# lockcontroller_V2.net
KiCad netlist of a schematic drawn in EAGLE
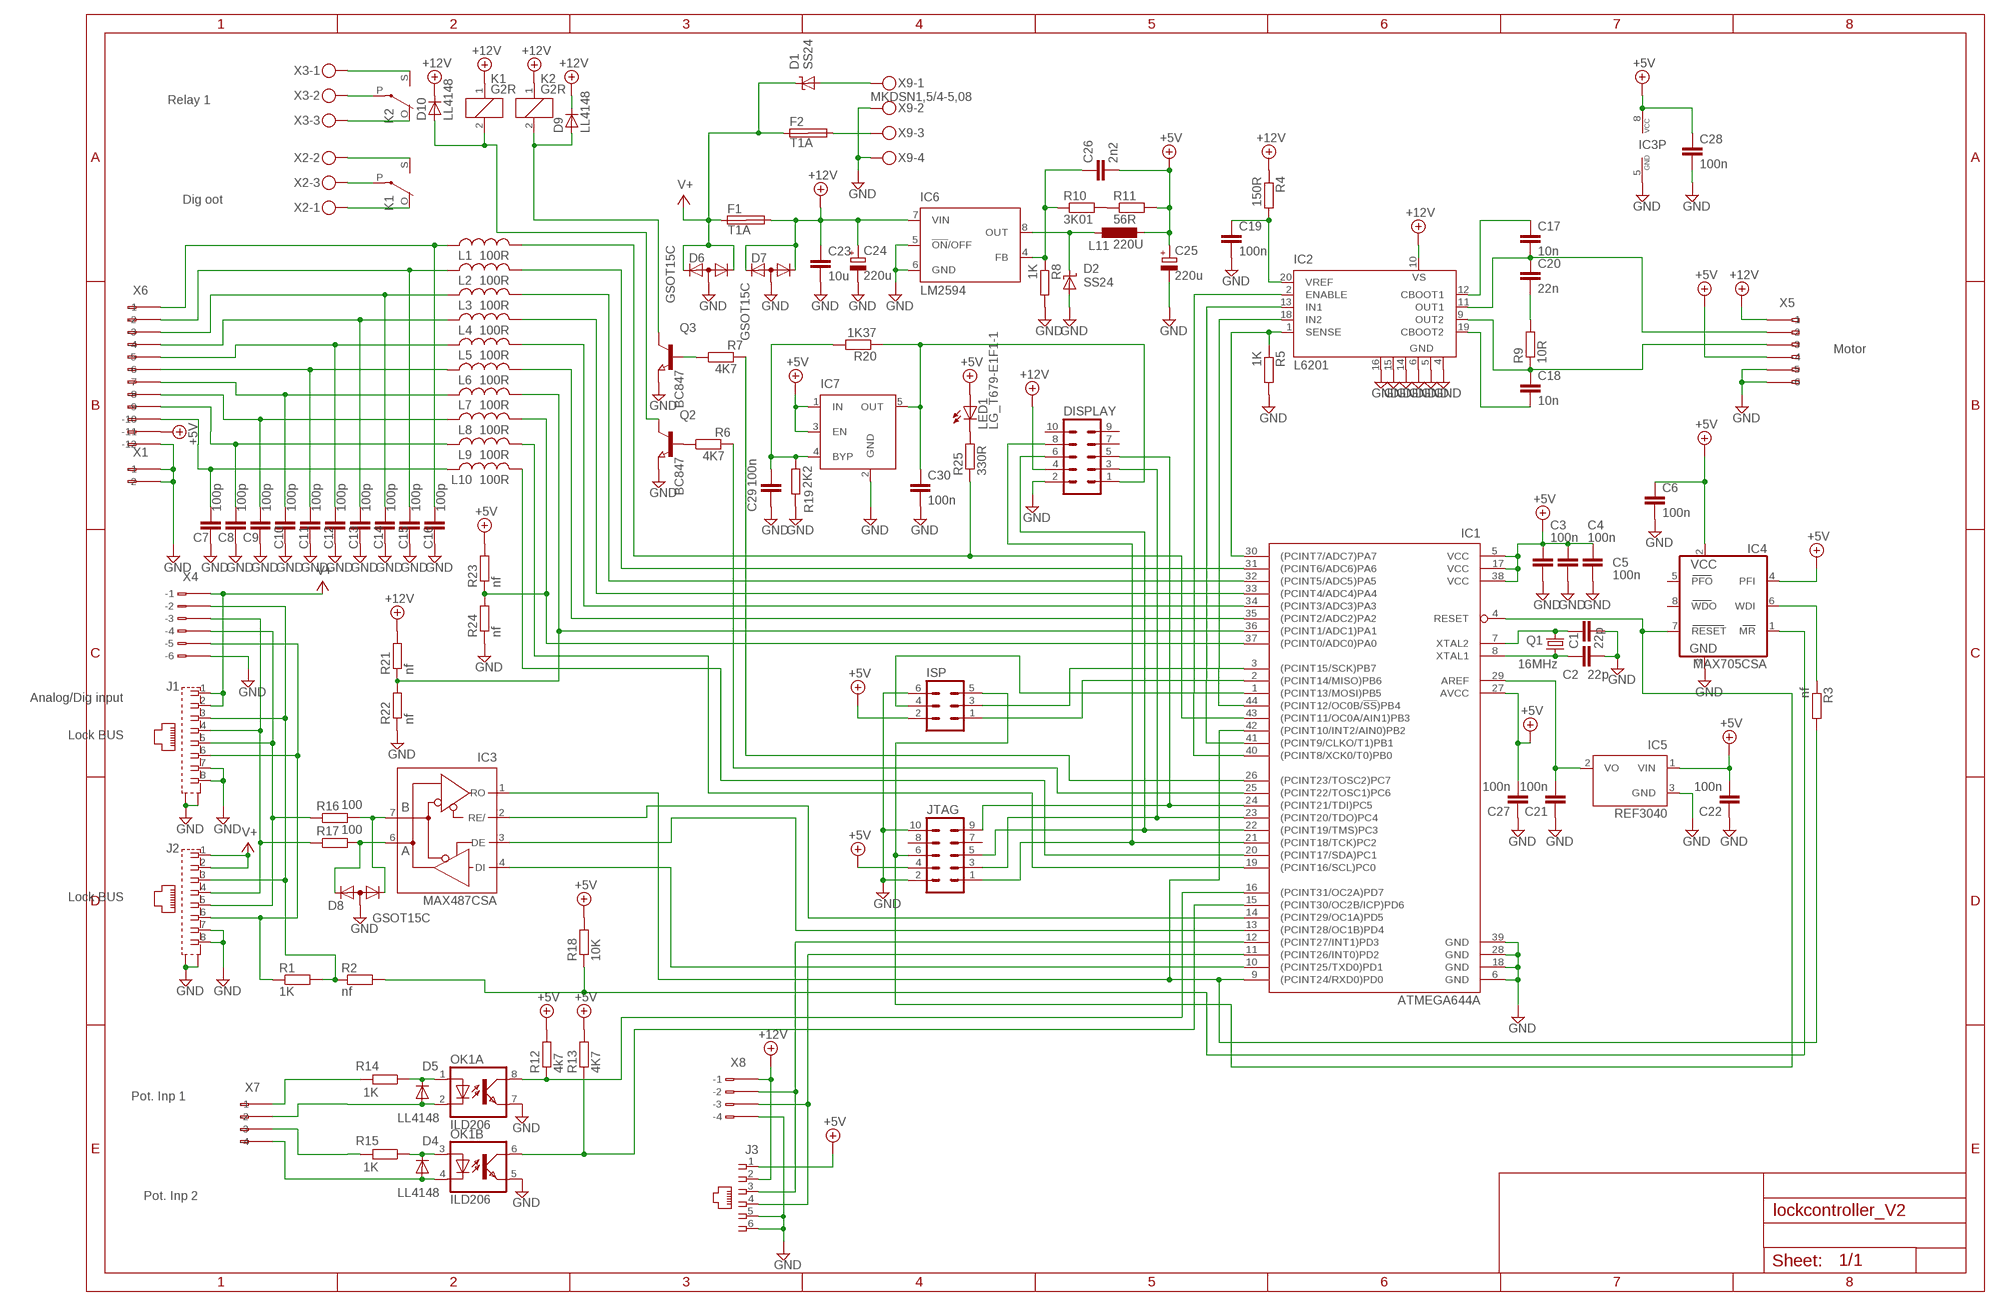
[diagram p0: schematic, sheet 1]

(export (version "E")
  (design (tool "Eeschema 10.0.6"))
  (components
    (comp (ref "C1")
      (value "22p")
      (footprint "eagle-import:C0603")
      (libsource (lib "eagle-import") (part "C-EUC0603"))
    )
    (comp (ref "C2")
      (value "22p")
      (footprint "eagle-import:C0603")
      (libsource (lib "eagle-import") (part "C-EUC0603"))
    )
    (comp (ref "C3")
      (value "100n")
      (footprint "eagle-import:C0603")
      (libsource (lib "eagle-import") (part "C-EUC0603"))
    )
    (comp (ref "C4")
      (value "100n")
      (footprint "eagle-import:C0603")
      (libsource (lib "eagle-import") (part "C-EUC0603"))
    )
    (comp (ref "C5")
      (value "100n")
      (footprint "eagle-import:C0603")
      (libsource (lib "eagle-import") (part "C-EUC0603"))
    )
    (comp (ref "C6")
      (value "100n")
      (footprint "eagle-import:C0603")
      (libsource (lib "eagle-import") (part "C-EUC0603"))
    )
    (comp (ref "C7")
      (value "100p")
      (footprint "eagle-import:C0603")
      (libsource (lib "eagle-import") (part "C-EUC0603"))
    )
    (comp (ref "C8")
      (value "100p")
      (footprint "eagle-import:C0603")
      (libsource (lib "eagle-import") (part "C-EUC0603"))
    )
    (comp (ref "C9")
      (value "100p")
      (footprint "eagle-import:C0603")
      (libsource (lib "eagle-import") (part "C-EUC0603"))
    )
    (comp (ref "C10")
      (value "100p")
      (footprint "eagle-import:C0603")
      (libsource (lib "eagle-import") (part "C-EUC0603"))
    )
    (comp (ref "C11")
      (value "100p")
      (footprint "eagle-import:C0603")
      (libsource (lib "eagle-import") (part "C-EUC0603"))
    )
    (comp (ref "C12")
      (value "100p")
      (footprint "eagle-import:C0603")
      (libsource (lib "eagle-import") (part "C-EUC0603"))
    )
    (comp (ref "C13")
      (value "100p")
      (footprint "eagle-import:C0603")
      (libsource (lib "eagle-import") (part "C-EUC0603"))
    )
    (comp (ref "C14")
      (value "100p")
      (footprint "eagle-import:C0603")
      (libsource (lib "eagle-import") (part "C-EUC0603"))
    )
    (comp (ref "C15")
      (value "100p")
      (footprint "eagle-import:C0603")
      (libsource (lib "eagle-import") (part "C-EUC0603"))
    )
    (comp (ref "C16")
      (value "100p")
      (footprint "eagle-import:C0603")
      (libsource (lib "eagle-import") (part "C-EUC0603"))
    )
    (comp (ref "C17")
      (value "10n")
      (footprint "eagle-import:C1206")
      (libsource (lib "eagle-import") (part "C-EUC1206"))
    )
    (comp (ref "C18")
      (value "10n")
      (footprint "eagle-import:C1206")
      (libsource (lib "eagle-import") (part "C-EUC1206"))
    )
    (comp (ref "C19")
      (value "100n")
      (footprint "eagle-import:C0603")
      (libsource (lib "eagle-import") (part "C-EUC0603"))
    )
    (comp (ref "C20")
      (value "22n")
      (footprint "eagle-import:C1206")
      (libsource (lib "eagle-import") (part "C-EUC1206"))
    )
    (comp (ref "C21")
      (value "100n")
      (footprint "eagle-import:C0603")
      (libsource (lib "eagle-import") (part "C-EUC0603"))
    )
    (comp (ref "C22")
      (value "100n")
      (footprint "eagle-import:C0603")
      (libsource (lib "eagle-import") (part "C-EUC0603"))
    )
    (comp (ref "C23")
      (value "10u")
      (footprint "eagle-import:C1210")
      (libsource (lib "eagle-import") (part "C-EUC1210"))
    )
    (comp (ref "C24")
      (value "220u")
      (footprint "eagle-import:E5-8,5")
      (libsource (lib "eagle-import") (part "CPOL-EUE5-8.5"))
    )
    (comp (ref "C25")
      (value "220u")
      (footprint "eagle-import:E5-8,5")
      (libsource (lib "eagle-import") (part "CPOL-EUE5-8.5"))
    )
    (comp (ref "C26")
      (value "2n2")
      (footprint "eagle-import:C0603")
      (libsource (lib "eagle-import") (part "C-EUC0603"))
    )
    (comp (ref "C27")
      (value "100n")
      (footprint "eagle-import:C0603")
      (libsource (lib "eagle-import") (part "C-EUC0603"))
    )
    (comp (ref "C28")
      (value "100n")
      (footprint "eagle-import:C0603")
      (libsource (lib "eagle-import") (part "C-EUC0603"))
    )
    (comp (ref "C29")
      (value "100n")
      (footprint "eagle-import:C0603")
      (libsource (lib "eagle-import") (part "C-EUC0603"))
    )
    (comp (ref "C30")
      (value "100n")
      (footprint "eagle-import:C0603")
      (libsource (lib "eagle-import") (part "C-EUC0603"))
    )
    (comp (ref "D1")
      (value "SS24")
      (footprint "eagle-import:SMBG")
      (libsource (lib "eagle-import") (part "SUPPRESSOR-SMBG"))
    )
    (comp (ref "D2")
      (value "SS24")
      (footprint "eagle-import:SMBG")
      (libsource (lib "eagle-import") (part "SUPPRESSOR-SMBG"))
    )
    (comp (ref "D4")
      (value "LL4148")
      (footprint "eagle-import:MELF-MLL34")
      (libsource (lib "eagle-import") (part "D-MLL-34"))
    )
    (comp (ref "D5")
      (value "LL4148")
      (footprint "eagle-import:MELF-MLL34")
      (libsource (lib "eagle-import") (part "D-MLL-34"))
    )
    (comp (ref "D6")
      (value "GSOT15C")
      (footprint "eagle-import:SOT23C")
      (libsource (lib "eagle-import") (part "DIODE_CA-AC__"))
    )
    (comp (ref "D7")
      (value "GSOT15C")
      (footprint "eagle-import:SOT23C")
      (libsource (lib "eagle-import") (part "DIODE_CA-AC__"))
    )
    (comp (ref "D8")
      (value "GSOT15C")
      (footprint "eagle-import:SOT23C")
      (libsource (lib "eagle-import") (part "DIODE_CA-AC__"))
    )
    (comp (ref "D9")
      (value "LL4148")
      (footprint "eagle-import:MELF-MLL34")
      (libsource (lib "eagle-import") (part "D-MLL-34"))
    )
    (comp (ref "D10")
      (value "LL4148")
      (footprint "eagle-import:MELF-MLL34")
      (libsource (lib "eagle-import") (part "D-MLL-34"))
    )
    (comp (ref "DISPLAY")
      (value "MA05-2")
      (footprint "eagle-import:MA05-2")
      (libsource (lib "eagle-import") (part "MA05-2"))
    )
    (comp (ref "F1")
      (value "T1A")
      (footprint "eagle-import:SHK20L")
      (libsource (lib "eagle-import") (part "SHK20L"))
    )
    (comp (ref "F2")
      (value "T1A")
      (footprint "eagle-import:SHK20L")
      (libsource (lib "eagle-import") (part "SHK20L"))
    )
    (comp (ref "IC1")
      (value "ATMEGA644A")
      (footprint "eagle-import:TQFP44")
      (libsource (lib "eagle-import") (part "ATMEGA644A"))
    )
    (comp (ref "IC2")
      (value "L6201")
      (footprint "eagle-import:SO20")
      (libsource (lib "eagle-import") (part "L6201"))
    )
    (comp (ref "IC3")
      (value "MAX487CSA")
      (footprint "eagle-import:SO08")
      (libsource (lib "eagle-import") (part "MAX481CSA"))
    )
    (comp (ref "IC4")
      (value "MAX705CSA")
      (footprint "eagle-import:SO08")
      (libsource (lib "eagle-import") (part "MAX705CSA"))
    )
    (comp (ref "IC5")
      (value "REF3040")
      (footprint "eagle-import:SOT23")
      (libsource (lib "eagle-import") (part "MC15TT25"))
    )
    (comp (ref "IC6")
      (value "LM2594")
      (footprint "eagle-import:SO08")
      (libsource (lib "eagle-import") (part "LM2594"))
    )
    (comp (ref "IC7")
      (value "MIC5219XX")
      (footprint "eagle-import:SOT23-5")
      (libsource (lib "eagle-import") (part "MIC5219XX"))
    )
    (comp (ref "ISP")
      (value "MA03-2")
      (footprint "eagle-import:MA03-2")
      (libsource (lib "eagle-import") (part "MA03-2"))
    )
    (comp (ref "J1")
      (value "555141-1")
      (footprint "eagle-import:555153-1")
      (libsource (lib "eagle-import") (part "555141-1"))
    )
    (comp (ref "J2")
      (value "555141-1")
      (footprint "eagle-import:555153-1")
      (libsource (lib "eagle-import") (part "555141-1"))
    )
    (comp (ref "J3")
      (value "520250-3")
      (footprint "eagle-import:520250-3")
      (libsource (lib "eagle-import") (part "520250-3"))
    )
    (comp (ref "JTAG")
      (value "MA05-2")
      (footprint "eagle-import:MA05-2")
      (libsource (lib "eagle-import") (part "MA05-2"))
    )
    (comp (ref "K1")
      (value "G2R")
      (footprint "eagle-import:G2R")
      (libsource (lib "eagle-import") (part "G2R"))
    )
    (comp (ref "K2")
      (value "G2R")
      (footprint "eagle-import:G2R")
      (libsource (lib "eagle-import") (part "G2R"))
    )
    (comp (ref "L1")
      (value "100R")
      (footprint "eagle-import:R0603")
      (libsource (lib "eagle-import") (part "L-US0603"))
    )
    (comp (ref "L2")
      (value "100R")
      (footprint "eagle-import:R0603")
      (libsource (lib "eagle-import") (part "L-US0603"))
    )
    (comp (ref "L3")
      (value "100R")
      (footprint "eagle-import:R0603")
      (libsource (lib "eagle-import") (part "L-US0603"))
    )
    (comp (ref "L4")
      (value "100R")
      (footprint "eagle-import:R0603")
      (libsource (lib "eagle-import") (part "L-US0603"))
    )
    (comp (ref "L5")
      (value "100R")
      (footprint "eagle-import:R0603")
      (libsource (lib "eagle-import") (part "L-US0603"))
    )
    (comp (ref "L6")
      (value "100R")
      (footprint "eagle-import:R0603")
      (libsource (lib "eagle-import") (part "L-US0603"))
    )
    (comp (ref "L7")
      (value "100R")
      (footprint "eagle-import:R0603")
      (libsource (lib "eagle-import") (part "L-US0603"))
    )
    (comp (ref "L8")
      (value "100R")
      (footprint "eagle-import:R0603")
      (libsource (lib "eagle-import") (part "L-US0603"))
    )
    (comp (ref "L9")
      (value "100R")
      (footprint "eagle-import:R0603")
      (libsource (lib "eagle-import") (part "L-US0603"))
    )
    (comp (ref "L10")
      (value "100R")
      (footprint "eagle-import:R0603")
      (libsource (lib "eagle-import") (part "L-US0603"))
    )
    (comp (ref "L11")
      (value "220U")
      (footprint "eagle-import:DO3316P")
      (libsource (lib "eagle-import") (part "DO3316P"))
    )
    (comp (ref "LED1")
      (value "LG_T679-E1F1-1")
      (footprint "eagle-import:PLCC2")
      (libsource (lib "eagle-import") (part "_T679-?-1E1F1LG"))
    )
    (comp (ref "OK1")
      (value "ILD206")
      (footprint "eagle-import:SOIC08")
      (libsource (lib "eagle-import") (part "ILD206"))
    )
    (comp (ref "Q1")
      (value "16MHz")
      (footprint "eagle-import:HC49_S")
      (libsource (lib "eagle-import") (part "CRYSTALHC49S"))
    )
    (comp (ref "Q2")
      (value "BC847")
      (footprint "eagle-import:SOT23")
      (libsource (lib "eagle-import") (part "NPN-TRANSISTOR_SOT23"))
    )
    (comp (ref "Q3")
      (value "BC847")
      (footprint "eagle-import:SOT23")
      (libsource (lib "eagle-import") (part "NPN-TRANSISTOR_SOT23"))
    )
    (comp (ref "R1")
      (value "1K")
      (footprint "eagle-import:R0603")
      (libsource (lib "eagle-import") (part "R-EU_R0603"))
    )
    (comp (ref "R2")
      (value "nf")
      (footprint "eagle-import:R0603")
      (libsource (lib "eagle-import") (part "R-EU_R0603"))
    )
    (comp (ref "R3")
      (value "nf")
      (footprint "eagle-import:R0603")
      (libsource (lib "eagle-import") (part "R-EU_R0603"))
    )
    (comp (ref "R4")
      (value "150R")
      (footprint "eagle-import:R0603")
      (libsource (lib "eagle-import") (part "R-EU_R0603"))
    )
    (comp (ref "R5")
      (value "1K")
      (footprint "eagle-import:R0603")
      (libsource (lib "eagle-import") (part "R-EU_R0603"))
    )
    (comp (ref "R6")
      (value "4K7")
      (footprint "eagle-import:R0603")
      (libsource (lib "eagle-import") (part "R-EU_R0603"))
    )
    (comp (ref "R7")
      (value "4K7")
      (footprint "eagle-import:R0603")
      (libsource (lib "eagle-import") (part "R-EU_R0603"))
    )
    (comp (ref "R8")
      (value "1K")
      (footprint "eagle-import:R0603")
      (libsource (lib "eagle-import") (part "R-EU_R0603"))
    )
    (comp (ref "R9")
      (value "10R")
      (footprint "eagle-import:R1206")
      (libsource (lib "eagle-import") (part "R-EU_R1206"))
    )
    (comp (ref "R10")
      (value "3K01")
      (footprint "eagle-import:R0603")
      (libsource (lib "eagle-import") (part "R-EU_R0603"))
    )
    (comp (ref "R11")
      (value "56R")
      (footprint "eagle-import:R0603")
      (libsource (lib "eagle-import") (part "R-EU_R0603"))
    )
    (comp (ref "R12")
      (value "4k7")
      (footprint "eagle-import:R0603")
      (libsource (lib "eagle-import") (part "R-EU_R0603"))
    )
    (comp (ref "R13")
      (value "4K7")
      (footprint "eagle-import:R0603")
      (libsource (lib "eagle-import") (part "R-EU_R0603"))
    )
    (comp (ref "R14")
      (value "1K")
      (footprint "eagle-import:R0603")
      (libsource (lib "eagle-import") (part "R-EU_R0603"))
    )
    (comp (ref "R15")
      (value "1K")
      (footprint "eagle-import:R0603")
      (libsource (lib "eagle-import") (part "R-EU_R0603"))
    )
    (comp (ref "R16")
      (value "100")
      (footprint "eagle-import:R0603")
      (libsource (lib "eagle-import") (part "R-EU_R0603"))
    )
    (comp (ref "R17")
      (value "100")
      (footprint "eagle-import:R0603")
      (libsource (lib "eagle-import") (part "R-EU_R0603"))
    )
    (comp (ref "R18")
      (value "10K")
      (footprint "eagle-import:R0603")
      (libsource (lib "eagle-import") (part "R-EU_R0603"))
    )
    (comp (ref "R19")
      (value "2K2")
      (footprint "eagle-import:R0603")
      (libsource (lib "eagle-import") (part "R-EU_R0603"))
    )
    (comp (ref "R20")
      (value "1K37")
      (footprint "eagle-import:R0603")
      (libsource (lib "eagle-import") (part "R-EU_R0603"))
    )
    (comp (ref "R21")
      (value "nf")
      (footprint "eagle-import:R0603")
      (libsource (lib "eagle-import") (part "R-EU_R0603"))
    )
    (comp (ref "R22")
      (value "nf")
      (footprint "eagle-import:R0603")
      (libsource (lib "eagle-import") (part "R-EU_R0603"))
    )
    (comp (ref "R23")
      (value "nf")
      (footprint "eagle-import:R0603")
      (libsource (lib "eagle-import") (part "R-EU_R0603"))
    )
    (comp (ref "R24")
      (value "nf")
      (footprint "eagle-import:R0603")
      (libsource (lib "eagle-import") (part "R-EU_R0603"))
    )
    (comp (ref "R25")
      (value "330R")
      (footprint "eagle-import:R0603")
      (libsource (lib "eagle-import") (part "R-EU_R0603"))
    )
    (comp (ref "X1")
      (value "233-502")
      (footprint "eagle-import:233-502")
      (libsource (lib "eagle-import") (part "233-502"))
    )
    (comp (ref "X2")
      (value "MKDSN1,5/3-5,08")
      (footprint "eagle-import:MKDSN1,5_3-5,08")
      (fields (field (name "MPN") "SMKDSN1,5/3-5,08"))
      (libsource (lib "eagle-import") (part "MKDSN1,5/3-5,08"))
    )
    (comp (ref "X3")
      (value "MKDSN1,5/3-5,08")
      (footprint "eagle-import:MKDSN1,5_3-5,08")
      (fields (field (name "MPN") "SMKDSN1,5/3-5,08"))
      (libsource (lib "eagle-import") (part "MKDSN1,5/3-5,08"))
    )
    (comp (ref "X4")
      (value "233-506")
      (footprint "eagle-import:233-506")
      (fields (field (name "MF") "Wago Corporation") (field (name "MPN") "0233-0506"))
      (libsource (lib "eagle-import") (part "233-506"))
    )
    (comp (ref "X5")
      (value "233-506")
      (footprint "eagle-import:233-506")
      (fields (field (name "MF") "Wago Corporation") (field (name "MPN") "0233-0506"))
      (libsource (lib "eagle-import") (part "con-wago255_233-506"))
    )
    (comp (ref "X6")
      (value "233-512")
      (footprint "eagle-import:233-512")
      (fields (field (name "MF") "Wago Corporation") (field (name "MPN") "0233-0512"))
      (libsource (lib "eagle-import") (part "233-512"))
    )
    (comp (ref "X7")
      (value "233-504")
      (footprint "eagle-import:233-504")
      (fields (field (name "MF") "Wago Corporation") (field (name "MPN") "0233-0504"))
      (libsource (lib "eagle-import") (part "con-wago255_233-504"))
    )
    (comp (ref "X8")
      (value "233-504")
      (footprint "eagle-import:233-504")
      (fields (field (name "MF") "Wago Corporation") (field (name "MPN") "0233-0504"))
      (libsource (lib "eagle-import") (part "233-504"))
    )
    (comp (ref "X9")
      (value "MKDSN1,5/4-5,08")
      (footprint "eagle-import:MKDSN1,5_4-5,08")
      (fields (field (name "MPN") "SMKDSN1,5/4-5,08"))
      (libsource (lib "eagle-import") (part "MKDSN1,5/4-5,08"))
    )
  )
  (nets
    (net (code "1") (name "+5V") (class "Default")
      (node (ref "C22") (pin "2") (pinfunction "2_2") (pintype "passive"))
      (node (ref "C25") (pin "+") (pinfunction "+_+") (pintype "passive"))
      (node (ref "C26") (pin "2") (pinfunction "2_2") (pintype "passive"))
      (node (ref "C27") (pin "2") (pinfunction "2_2") (pintype "passive"))
      (node (ref "C28") (pin "1") (pinfunction "1_1") (pintype "passive"))
      (node (ref "C3") (pin "1") (pinfunction "1_1") (pintype "passive"))
      (node (ref "C4") (pin "1") (pinfunction "1_1") (pintype "passive"))
      (node (ref "C5") (pin "1") (pinfunction "1_1") (pintype "passive"))
      (node (ref "C6") (pin "1") (pinfunction "1_1") (pintype "passive"))
      (node (ref "IC1") (pin "17") (pinfunction "VCC_17") (pintype "power_in"))
      (node (ref "IC1") (pin "27") (pinfunction "AVCC_27") (pintype "power_in"))
      (node (ref "IC1") (pin "38") (pinfunction "VCC_38") (pintype "power_in"))
      (node (ref "IC1") (pin "5") (pinfunction "VCC_5") (pintype "power_in"))
      (node (ref "IC3") (pin "8") (pinfunction "VCC_8") (pintype "power_in"))
      (node (ref "IC4") (pin "2") (pinfunction "VCC_2") (pintype "power_in"))
      (node (ref "IC4") (pin "4") (pinfunction "PFI_4") (pintype "input"))
      (node (ref "IC5") (pin "1") (pinfunction "VIN_1") (pintype "input"))
      (node (ref "IC7") (pin "1") (pinfunction "IN_1") (pintype "input"))
      (node (ref "IC7") (pin "3") (pinfunction "EN_3") (pintype "input"))
      (node (ref "ISP") (pin "2") (pinfunction "2_2") (pintype "passive"))
      (node (ref "J3") (pin "1") (pinfunction "1_1") (pintype "passive"))
      (node (ref "JTAG") (pin "4") (pinfunction "4_4") (pintype "passive"))
      (node (ref "L11") (pin "2") (pinfunction "2_2") (pintype "passive"))
      (node (ref "LED1") (pin "A") (pinfunction "A_A") (pintype "passive"))
      (node (ref "R11") (pin "2") (pinfunction "2_2") (pintype "passive"))
      (node (ref "R12") (pin "2") (pinfunction "2_2") (pintype "passive"))
      (node (ref "R13") (pin "2") (pinfunction "2_2") (pintype "passive"))
      (node (ref "R18") (pin "2") (pinfunction "2_2") (pintype "passive"))
      (node (ref "R23") (pin "2") (pinfunction "2_2") (pintype "passive"))
      (node (ref "X5") (pin "A4") (pinfunction "-4_A4") (pintype "passive"))
      (node (ref "X6") (pin "A11") (pinfunction "-11_A11") (pintype "passive"))
    )
    (net (code "2") (name "+12V") (class "Default")
      (node (ref "C23") (pin "1") (pinfunction "1_1") (pintype "passive"))
      (node (ref "C24") (pin "+") (pinfunction "+_+") (pintype "passive"))
      (node (ref "D10") (pin "1") (pinfunction "C_1") (pintype "passive"))
      (node (ref "D7") (pin "1") (pinfunction "K1_1") (pintype "passive"))
      (node (ref "D7") (pin "2") (pinfunction "K2_2") (pintype "passive"))
      (node (ref "D9") (pin "1") (pinfunction "C_1") (pintype "passive"))
      (node (ref "DISPLAY") (pin "4") (pinfunction "4_4") (pintype "passive"))
      (node (ref "F1") (pin "2A") (pinfunction "2A_2A") (pintype "passive"))
      (node (ref "IC2") (pin "10") (pinfunction "VS_10") (pintype "power_in"))
      (node (ref "IC6") (pin "7") (pinfunction "VIN_7") (pintype "input"))
      (node (ref "J3") (pin "2") (pinfunction "2_2") (pintype "passive"))
      (node (ref "K1") (pin "1") (pinfunction "1_1") (pintype "passive"))
      (node (ref "K2") (pin "1") (pinfunction "1_1") (pintype "passive"))
      (node (ref "R21") (pin "2") (pinfunction "2_2") (pintype "passive"))
      (node (ref "R4") (pin "1") (pinfunction "1_1") (pintype "passive"))
      (node (ref "X5") (pin "A1") (pinfunction "-1_A1") (pintype "passive"))
      (node (ref "X8") (pin "B1") (pinfunction "B-1_B1") (pintype "passive"))
    )
    (net (code "3") (name "GND") (class "Default")
      (node (ref "C1") (pin "2") (pinfunction "2_2") (pintype "passive"))
      (node (ref "C10") (pin "2") (pinfunction "2_2") (pintype "passive"))
      (node (ref "C11") (pin "2") (pinfunction "2_2") (pintype "passive"))
      (node (ref "C12") (pin "2") (pinfunction "2_2") (pintype "passive"))
      (node (ref "C13") (pin "2") (pinfunction "2_2") (pintype "passive"))
      (node (ref "C14") (pin "2") (pinfunction "2_2") (pintype "passive"))
      (node (ref "C15") (pin "2") (pinfunction "2_2") (pintype "passive"))
      (node (ref "C16") (pin "2") (pinfunction "2_2") (pintype "passive"))
      (node (ref "C19") (pin "2") (pinfunction "2_2") (pintype "passive"))
      (node (ref "C2") (pin "2") (pinfunction "2_2") (pintype "passive"))
      (node (ref "C21") (pin "1") (pinfunction "1_1") (pintype "passive"))
      (node (ref "C22") (pin "1") (pinfunction "1_1") (pintype "passive"))
      (node (ref "C23") (pin "2") (pinfunction "2_2") (pintype "passive"))
      (node (ref "C24") (pin "-") (pinfunction "-_-") (pintype "passive"))
      (node (ref "C25") (pin "-") (pinfunction "-_-") (pintype "passive"))
      (node (ref "C27") (pin "1") (pinfunction "1_1") (pintype "passive"))
      (node (ref "C28") (pin "2") (pinfunction "2_2") (pintype "passive"))
      (node (ref "C29") (pin "2") (pinfunction "2_2") (pintype "passive"))
      (node (ref "C3") (pin "2") (pinfunction "2_2") (pintype "passive"))
      (node (ref "C30") (pin "2") (pinfunction "2_2") (pintype "passive"))
      (node (ref "C4") (pin "2") (pinfunction "2_2") (pintype "passive"))
      (node (ref "C5") (pin "2") (pinfunction "2_2") (pintype "passive"))
      (node (ref "C6") (pin "2") (pinfunction "2_2") (pintype "passive"))
      (node (ref "C7") (pin "2") (pinfunction "2_2") (pintype "passive"))
      (node (ref "C8") (pin "2") (pinfunction "2_2") (pintype "passive"))
      (node (ref "C9") (pin "2") (pinfunction "2_2") (pintype "passive"))
      (node (ref "D2") (pin "A") (pinfunction "A_A") (pintype "passive"))
      (node (ref "D6") (pin "3") (pinfunction "A_3") (pintype "passive"))
      (node (ref "D7") (pin "3") (pinfunction "A_3") (pintype "passive"))
      (node (ref "D8") (pin "3") (pinfunction "A_3") (pintype "passive"))
      (node (ref "DISPLAY") (pin "2") (pinfunction "2_2") (pintype "passive"))
      (node (ref "IC1") (pin "18") (pinfunction "GND_18") (pintype "power_in"))
      (node (ref "IC1") (pin "28") (pinfunction "GND_28") (pintype "power_in"))
      (node (ref "IC1") (pin "39") (pinfunction "GND_39") (pintype "power_in"))
      (node (ref "IC1") (pin "6") (pinfunction "GND_6") (pintype "power_in"))
      (node (ref "IC2") (pin "14") (pinfunction "GND_14") (pintype "power_in"))
      (node (ref "IC2") (pin "15") (pinfunction "GND_15") (pintype "power_in"))
      (node (ref "IC2") (pin "16") (pinfunction "GND_16") (pintype "power_in"))
      (node (ref "IC2") (pin "4") (pinfunction "GND_4") (pintype "power_in"))
      (node (ref "IC2") (pin "5") (pinfunction "GND_5") (pintype "power_in"))
      (node (ref "IC2") (pin "6") (pinfunction "GND_6") (pintype "power_in"))
      (node (ref "IC3") (pin "5") (pinfunction "GND_5") (pintype "power_in"))
      (node (ref "IC4") (pin "3") (pinfunction "GND_3") (pintype "power_in"))
      (node (ref "IC5") (pin "3") (pinfunction "GND_3") (pintype "passive"))
      (node (ref "IC6") (pin "5") (pinfunction "~{ON}/OFF_5") (pintype "input"))
      (node (ref "IC6") (pin "6") (pinfunction "GND_6") (pintype "power_in"))
      (node (ref "IC7") (pin "2") (pinfunction "GND_2") (pintype "power_in"))
      (node (ref "ISP") (pin "6") (pinfunction "6_6") (pintype "passive"))
      (node (ref "J1") (pin "7") (pinfunction "7_7") (pintype "passive"))
      (node (ref "J1") (pin "8") (pinfunction "8_8") (pintype "passive"))
      (node (ref "J1") (pin "G1") (pinfunction "S1_G1") (pintype "passive"))
      (node (ref "J1") (pin "G2") (pinfunction "S2_G2") (pintype "passive"))
      (node (ref "J2") (pin "7") (pinfunction "7_7") (pintype "passive"))
      (node (ref "J2") (pin "8") (pinfunction "8_8") (pintype "passive"))
      (node (ref "J2") (pin "G1") (pinfunction "S1_G1") (pintype "passive"))
      (node (ref "J2") (pin "G2") (pinfunction "S2_G2") (pintype "passive"))
      (node (ref "J3") (pin "5") (pinfunction "5_5") (pintype "passive"))
      (node (ref "J3") (pin "6") (pinfunction "6_6") (pintype "passive"))
      (node (ref "JTAG") (pin "10") (pinfunction "10_10") (pintype "passive"))
      (node (ref "JTAG") (pin "2") (pinfunction "2_2") (pintype "passive"))
      (node (ref "OK1") (pin "5") (pinfunction "EMIT_5") (pintype "passive"))
      (node (ref "OK1") (pin "7") (pinfunction "EMIT_7") (pintype "passive"))
      (node (ref "Q2") (pin "2") (pinfunction "E_2") (pintype "passive"))
      (node (ref "Q3") (pin "2") (pinfunction "E_2") (pintype "passive"))
      (node (ref "R19") (pin "1") (pinfunction "1_1") (pintype "passive"))
      (node (ref "R22") (pin "1") (pinfunction "1_1") (pintype "passive"))
      (node (ref "R24") (pin "1") (pinfunction "1_1") (pintype "passive"))
      (node (ref "R5") (pin "2") (pinfunction "2_2") (pintype "passive"))
      (node (ref "R8") (pin "2") (pinfunction "2_2") (pintype "passive"))
      (node (ref "X1") (pin "A1") (pinfunction "-1_A1") (pintype "passive"))
      (node (ref "X1") (pin "A2") (pinfunction "-2_A2") (pintype "passive"))
      (node (ref "X4") (pin "B6") (pinfunction "B-6_B6") (pintype "passive"))
      (node (ref "X5") (pin "A5") (pinfunction "-5_A5") (pintype "passive"))
      (node (ref "X5") (pin "A6") (pinfunction "-6_A6") (pintype "passive"))
      (node (ref "X6") (pin "A12") (pinfunction "-12_A12") (pintype "passive"))
      (node (ref "X8") (pin "B4") (pinfunction "B-4_B4") (pintype "passive"))
      (node (ref "X9") (pin "2") (pinfunction "KL_2") (pintype "passive"))
      (node (ref "X9") (pin "4") (pinfunction "KL_4") (pintype "passive"))
    )
    (net (code "4") (name "Net-(C20-Pad2)") (class "Default")
      (node (ref "C20") (pin "2") (pinfunction "2_2") (pintype "passive"))
      (node (ref "R9") (pin "2") (pinfunction "2_2") (pintype "passive"))
    )
    (net (code "5") (name "Net-(D4-A)") (class "Default")
      (node (ref "D4") (pin "2") (pinfunction "A_2") (pintype "passive"))
      (node (ref "OK1") (pin "4") (pinfunction "C_4") (pintype "passive"))
      (node (ref "X7") (pin "A4") (pinfunction "-4_A4") (pintype "passive"))
    )
    (net (code "6") (name "Net-(D4-C)") (class "Default")
      (node (ref "D4") (pin "1") (pinfunction "C_1") (pintype "passive"))
      (node (ref "OK1") (pin "3") (pinfunction "A_3") (pintype "passive"))
      (node (ref "R15") (pin "1") (pinfunction "1_1") (pintype "passive"))
    )
    (net (code "7") (name "Net-(D5-A)") (class "Default")
      (node (ref "D5") (pin "2") (pinfunction "A_2") (pintype "passive"))
      (node (ref "OK1") (pin "2") (pinfunction "C_2") (pintype "passive"))
      (node (ref "X7") (pin "A2") (pinfunction "-2_A2") (pintype "passive"))
    )
    (net (code "8") (name "Net-(D5-C)") (class "Default")
      (node (ref "D5") (pin "1") (pinfunction "C_1") (pintype "passive"))
      (node (ref "OK1") (pin "1") (pinfunction "A_1") (pintype "passive"))
      (node (ref "R14") (pin "1") (pinfunction "1_1") (pintype "passive"))
    )
    (net (code "9") (name "Net-(D8-K1)") (class "Default")
      (node (ref "D8") (pin "1") (pinfunction "K1_1") (pintype "passive"))
      (node (ref "IC3") (pin "7") (pinfunction "B_7") (pintype "passive"))
      (node (ref "R16") (pin "2") (pinfunction "2_2") (pintype "passive"))
    )
    (net (code "10") (name "Net-(D8-K2)") (class "Default")
      (node (ref "D8") (pin "2") (pinfunction "K2_2") (pintype "passive"))
      (node (ref "IC3") (pin "6") (pinfunction "A_6") (pintype "passive"))
      (node (ref "R17") (pin "2") (pinfunction "2_2") (pintype "passive"))
    )
    (net (code "11") (name "Net-(D9-A)") (class "Default")
      (node (ref "D9") (pin "2") (pinfunction "A_2") (pintype "passive"))
      (node (ref "K2") (pin "2") (pinfunction "2_2") (pintype "passive"))
      (node (ref "Q3") (pin "3") (pinfunction "C_3") (pintype "passive"))
    )
    (net (code "12") (name "Net-(D10-A)") (class "Default")
      (node (ref "D10") (pin "2") (pinfunction "A_2") (pintype "passive"))
      (node (ref "K1") (pin "2") (pinfunction "2_2") (pintype "passive"))
      (node (ref "Q2") (pin "3") (pinfunction "C_3") (pintype "passive"))
    )
    (net (code "13") (name "Net-(IC1-(PCINT0{slash}ADC0)PA0)") (class "Default")
      (node (ref "IC1") (pin "37") (pinfunction "(PCINT0/ADC0)PA0_37") (pintype "bidirectional"))
      (node (ref "L8") (pin "2") (pinfunction "2_2") (pintype "passive"))
      (node (ref "R23") (pin "1") (pinfunction "1_1") (pintype "passive"))
      (node (ref "R24") (pin "2") (pinfunction "2_2") (pintype "passive"))
    )
    (net (code "14") (name "Net-(IC1-(PCINT1{slash}ADC1)PA1)") (class "Default")
      (node (ref "IC1") (pin "36") (pinfunction "(PCINT1/ADC1)PA1_36") (pintype "bidirectional"))
      (node (ref "L7") (pin "2") (pinfunction "2_2") (pintype "passive"))
      (node (ref "R21") (pin "1") (pinfunction "1_1") (pintype "passive"))
      (node (ref "R22") (pin "2") (pinfunction "2_2") (pintype "passive"))
    )
    (net (code "15") (name "Net-(IC1-(PCINT2{slash}ADC2)PA2)") (class "Default")
      (node (ref "IC1") (pin "35") (pinfunction "(PCINT2/ADC2)PA2_35") (pintype "bidirectional"))
      (node (ref "L6") (pin "2") (pinfunction "2_2") (pintype "passive"))
    )
    (net (code "16") (name "Net-(IC1-(PCINT3{slash}ADC3)PA3)") (class "Default")
      (node (ref "IC1") (pin "34") (pinfunction "(PCINT3/ADC3)PA3_34") (pintype "bidirectional"))
      (node (ref "L5") (pin "2") (pinfunction "2_2") (pintype "passive"))
    )
    (net (code "17") (name "Net-(IC1-(PCINT4{slash}ADC4)PA4)") (class "Default")
      (node (ref "IC1") (pin "33") (pinfunction "(PCINT4/ADC4)PA4_33") (pintype "bidirectional"))
      (node (ref "L4") (pin "2") (pinfunction "2_2") (pintype "passive"))
    )
    (net (code "18") (name "Net-(IC1-(PCINT5{slash}ADC5)PA5)") (class "Default")
      (node (ref "IC1") (pin "32") (pinfunction "(PCINT5/ADC5)PA5_32") (pintype "bidirectional"))
      (node (ref "L3") (pin "2") (pinfunction "2_2") (pintype "passive"))
    )
    (net (code "19") (name "Net-(IC1-(PCINT6{slash}ADC6)PA6)") (class "Default")
      (node (ref "IC1") (pin "31") (pinfunction "(PCINT6/ADC6)PA6_31") (pintype "bidirectional"))
      (node (ref "L2") (pin "2") (pinfunction "2_2") (pintype "passive"))
    )
    (net (code "20") (name "Net-(IC1-(PCINT7{slash}ADC7)PA7)") (class "Default")
      (node (ref "IC1") (pin "30") (pinfunction "(PCINT7/ADC7)PA7_30") (pintype "bidirectional"))
      (node (ref "IC2") (pin "1") (pinfunction "SENSE_1") (pintype "input"))
      (node (ref "R5") (pin "1") (pinfunction "1_1") (pintype "passive"))
    )
    (net (code "21") (name "Net-(IC1-(PCINT8{slash}XCK0{slash}T0)PB0)") (class "Default")
      (node (ref "IC1") (pin "40") (pinfunction "(PCINT8/XCK0/T0)PB0_40") (pintype "bidirectional"))
      (node (ref "IC2") (pin "2") (pinfunction "ENABLE_2") (pintype "input"))
    )
    (net (code "22") (name "Net-(IC1-(PCINT9{slash}CLKO{slash}T1)PB1)") (class "Default")
      (node (ref "IC1") (pin "41") (pinfunction "(PCINT9/CLKO/T1)PB1_41") (pintype "bidirectional"))
      (node (ref "IC2") (pin "13") (pinfunction "IN1_13") (pintype "input"))
    )
    (net (code "23") (name "Net-(IC1-(PCINT10{slash}INT2{slash}AIN0)PB2)") (class "Default")
      (node (ref "IC1") (pin "42") (pinfunction "(PCINT10/INT2/AIN0)PB2_42") (pintype "bidirectional"))
      (node (ref "IC1") (pin "9") (pinfunction "(PCINT24/RXD0)PD0_9") (pintype "bidirectional"))
      (node (ref "IC3") (pin "1") (pinfunction "RO_1") (pintype "output"))
      (node (ref "R3") (pin "2") (pinfunction "2_2") (pintype "passive"))
    )
    (net (code "24") (name "Net-(IC1-(PCINT11{slash}OC0A{slash}AIN1)PB3)") (class "Default")
      (node (ref "IC1") (pin "43") (pinfunction "(PCINT11/OC0A/AIN1)PB3_43") (pintype "bidirectional"))
      (node (ref "L1") (pin "2") (pinfunction "2_2") (pintype "passive"))
      (node (ref "R25") (pin "1") (pinfunction "1_1") (pintype "passive"))
    )
    (net (code "25") (name "Net-(IC1-(PCINT12{slash}OC0B{slash}~{SS})PB4)") (class "Default")
      (node (ref "IC1") (pin "44") (pinfunction "(PCINT12/OC0B/~{SS})PB4_44") (pintype "bidirectional"))
      (node (ref "IC2") (pin "18") (pinfunction "IN2_18") (pintype "input"))
    )
    (net (code "26") (name "Net-(IC1-(PCINT13{slash}MOSI)PB5)") (class "Default")
      (node (ref "IC1") (pin "1") (pinfunction "(PCINT13/MOSI)PB5_1") (pintype "bidirectional"))
      (node (ref "ISP") (pin "4") (pinfunction "4_4") (pintype "passive"))
    )
    (net (code "27") (name "Net-(IC1-(PCINT14{slash}MISO)PB6)") (class "Default")
      (node (ref "IC1") (pin "2") (pinfunction "(PCINT14/MISO)PB6_2") (pintype "bidirectional"))
      (node (ref "ISP") (pin "1") (pinfunction "1_1") (pintype "passive"))
    )
    (net (code "28") (name "Net-(IC1-(PCINT15{slash}SCK)PB7)") (class "Default")
      (node (ref "IC1") (pin "3") (pinfunction "(PCINT15/SCK)PB7_3") (pintype "bidirectional"))
      (node (ref "ISP") (pin "3") (pinfunction "3_3") (pintype "passive"))
    )
    (net (code "29") (name "Net-(IC1-(PCINT16{slash}SCL)PC0)") (class "Default")
      (node (ref "IC1") (pin "19") (pinfunction "(PCINT16/SCL)PC0_19") (pintype "output"))
      (node (ref "L9") (pin "2") (pinfunction "2_2") (pintype "passive"))
    )
    (net (code "30") (name "Net-(IC1-(PCINT17{slash}SDA)PC1)") (class "Default")
      (node (ref "IC1") (pin "20") (pinfunction "(PCINT17/SDA)PC1_20") (pintype "output"))
      (node (ref "L10") (pin "2") (pinfunction "2_2") (pintype "passive"))
    )
    (net (code "31") (name "Net-(IC1-(PCINT18{slash}TCK)PC2)") (class "Default")
      (node (ref "DISPLAY") (pin "8") (pinfunction "8_8") (pintype "passive"))
      (node (ref "IC1") (pin "21") (pinfunction "(PCINT18/TCK)PC2_21") (pintype "output"))
      (node (ref "JTAG") (pin "1") (pinfunction "1_1") (pintype "passive"))
    )
    (net (code "32") (name "Net-(IC1-(PCINT19{slash}TMS)PC3)") (class "Default")
      (node (ref "DISPLAY") (pin "6") (pinfunction "6_6") (pintype "passive"))
      (node (ref "IC1") (pin "22") (pinfunction "(PCINT19/TMS)PC3_22") (pintype "output"))
      (node (ref "JTAG") (pin "5") (pinfunction "5_5") (pintype "passive"))
    )
    (net (code "33") (name "Net-(IC1-(PCINT20{slash}TDO)PC4)") (class "Default")
      (node (ref "DISPLAY") (pin "3") (pinfunction "3_3") (pintype "passive"))
      (node (ref "IC1") (pin "23") (pinfunction "(PCINT20/TDO)PC4_23") (pintype "output"))
      (node (ref "JTAG") (pin "3") (pinfunction "3_3") (pintype "passive"))
    )
    (net (code "34") (name "Net-(IC1-(PCINT21{slash}TDI)PC5)") (class "Default")
      (node (ref "DISPLAY") (pin "5") (pinfunction "5_5") (pintype "passive"))
      (node (ref "IC1") (pin "24") (pinfunction "(PCINT21/TDI)PC5_24") (pintype "output"))
      (node (ref "JTAG") (pin "9") (pinfunction "9_9") (pintype "passive"))
    )
    (net (code "35") (name "Net-(IC1-(PCINT22{slash}TOSC1)PC6)") (class "Default")
      (node (ref "IC1") (pin "25") (pinfunction "(PCINT22/TOSC1)PC6_25") (pintype "output"))
      (node (ref "R6") (pin "2") (pinfunction "2_2") (pintype "passive"))
    )
    (net (code "36") (name "Net-(IC1-(PCINT23{slash}TOSC2)PC7)") (class "Default")
      (node (ref "IC1") (pin "26") (pinfunction "(PCINT23/TOSC2)PC7_26") (pintype "output"))
      (node (ref "R7") (pin "2") (pinfunction "2_2") (pintype "passive"))
    )
    (net (code "37") (name "Net-(IC1-(PCINT25{slash}TXD0)PD1)") (class "Default")
      (node (ref "IC1") (pin "10") (pinfunction "(PCINT25/TXD0)PD1_10") (pintype "bidirectional"))
      (node (ref "IC3") (pin "4") (pinfunction "DI_4") (pintype "input"))
    )
    (net (code "38") (name "Net-(IC1-(PCINT26{slash}INT0)PD2)") (class "Default")
      (node (ref "IC1") (pin "11") (pinfunction "(PCINT26/INT0)PD2_11") (pintype "bidirectional"))
      (node (ref "J3") (pin "4") (pinfunction "4_4") (pintype "passive"))
      (node (ref "X8") (pin "B3") (pinfunction "B-3_B3") (pintype "passive"))
    )
    (net (code "39") (name "Net-(IC1-(PCINT27{slash}INT1)PD3)") (class "Default")
      (node (ref "IC1") (pin "12") (pinfunction "(PCINT27/INT1)PD3_12") (pintype "bidirectional"))
      (node (ref "J3") (pin "3") (pinfunction "3_3") (pintype "passive"))
      (node (ref "X8") (pin "B2") (pinfunction "B-2_B2") (pintype "passive"))
    )
    (net (code "40") (name "Net-(IC1-(PCINT28{slash}OC1B)PD4)") (class "Default")
      (node (ref "IC1") (pin "13") (pinfunction "(PCINT28/OC1B)PD4_13") (pintype "bidirectional"))
      (node (ref "IC3") (pin "3") (pinfunction "DE_3") (pintype "input"))
    )
    (net (code "41") (name "Net-(IC1-(PCINT29{slash}OC1A)PD5)") (class "Default")
      (node (ref "IC1") (pin "14") (pinfunction "(PCINT29/OC1A)PD5_14") (pintype "bidirectional"))
      (node (ref "IC3") (pin "2") (pinfunction "RE/_2") (pintype "input"))
    )
    (net (code "42") (name "Net-(IC1-(PCINT30{slash}OC2B{slash}ICP)PD6)") (class "Default")
      (node (ref "IC1") (pin "15") (pinfunction "(PCINT30/OC2B/ICP)PD6_15") (pintype "bidirectional"))
      (node (ref "OK1") (pin "6") (pinfunction "COL_6") (pintype "passive"))
      (node (ref "R13") (pin "1") (pinfunction "1_1") (pintype "passive"))
    )
    (net (code "43") (name "Net-(IC1-(PCINT31{slash}OC2A)PD7)") (class "Default")
      (node (ref "IC1") (pin "16") (pinfunction "(PCINT31/OC2A)PD7_16") (pintype "bidirectional"))
      (node (ref "OK1") (pin "8") (pinfunction "COL_8") (pintype "passive"))
      (node (ref "R12") (pin "1") (pinfunction "1_1") (pintype "passive"))
    )
    (net (code "44") (name "Net-(IC1-AREF)") (class "Default")
      (node (ref "C21") (pin "2") (pinfunction "2_2") (pintype "passive"))
      (node (ref "IC1") (pin "29") (pinfunction "AREF_29") (pintype "passive"))
      (node (ref "IC5") (pin "2") (pinfunction "VO_2") (pintype "output"))
    )
    (net (code "45") (name "Net-(IC1-RESET)") (class "Default")
      (node (ref "IC1") (pin "4") (pinfunction "RESET_4") (pintype "input"))
      (node (ref "IC4") (pin "7") (pinfunction "RESET_7") (pintype "output"))
      (node (ref "ISP") (pin "5") (pinfunction "5_5") (pintype "passive"))
      (node (ref "JTAG") (pin "6") (pinfunction "6_6") (pintype "passive"))
    )
    (net (code "46") (name "Net-(IC1-XTAL1)") (class "Default")
      (node (ref "C2") (pin "1") (pinfunction "1_1") (pintype "passive"))
      (node (ref "IC1") (pin "8") (pinfunction "XTAL1_8") (pintype "bidirectional"))
      (node (ref "Q1") (pin "1") (pinfunction "1_1") (pintype "passive"))
    )
    (net (code "47") (name "Net-(IC1-XTAL2)") (class "Default")
      (node (ref "C1") (pin "1") (pinfunction "1_1") (pintype "passive"))
      (node (ref "IC1") (pin "7") (pinfunction "XTAL2_7") (pintype "bidirectional"))
      (node (ref "Q1") (pin "2") (pinfunction "2_2") (pintype "passive"))
    )
    (net (code "48") (name "Net-(IC2-CBOOT1)") (class "Default")
      (node (ref "C17") (pin "1") (pinfunction "1_1") (pintype "passive"))
      (node (ref "IC2") (pin "12") (pinfunction "CBOOT1_12") (pintype "input"))
    )
    (net (code "49") (name "Net-(IC2-CBOOT2)") (class "Default")
      (node (ref "C18") (pin "2") (pinfunction "2_2") (pintype "passive"))
      (node (ref "IC2") (pin "19") (pinfunction "CBOOT2_19") (pintype "input"))
    )
    (net (code "50") (name "Net-(IC2-OUT1)") (class "Default")
      (node (ref "C17") (pin "2") (pinfunction "2_2") (pintype "passive"))
      (node (ref "C20") (pin "1") (pinfunction "1_1") (pintype "passive"))
      (node (ref "IC2") (pin "11") (pinfunction "OUT1_11") (pintype "output"))
      (node (ref "X5") (pin "A2") (pinfunction "-2_A2") (pintype "passive"))
    )
    (net (code "51") (name "Net-(IC2-OUT2)") (class "Default")
      (node (ref "C18") (pin "1") (pinfunction "1_1") (pintype "passive"))
      (node (ref "IC2") (pin "9") (pinfunction "OUT2_9") (pintype "output"))
      (node (ref "R9") (pin "1") (pinfunction "1_1") (pintype "passive"))
      (node (ref "X5") (pin "A3") (pinfunction "-3_A3") (pintype "passive"))
    )
    (net (code "52") (name "Net-(IC2-VREF)") (class "Default")
      (node (ref "C19") (pin "1") (pinfunction "1_1") (pintype "passive"))
      (node (ref "IC2") (pin "20") (pinfunction "VREF_20") (pintype "input"))
      (node (ref "R4") (pin "2") (pinfunction "2_2") (pintype "passive"))
    )
    (net (code "53") (name "Net-(IC4-MR)") (class "Default")
      (node (ref "IC4") (pin "1") (pinfunction "MR_1") (pintype "input"))
      (node (ref "R18") (pin "1") (pinfunction "1_1") (pintype "passive"))
      (node (ref "R2") (pin "2") (pinfunction "2_2") (pintype "passive"))
    )
    (net (code "54") (name "Net-(IC4-WDI)") (class "Default")
      (node (ref "IC4") (pin "6") (pinfunction "WDI_6") (pintype "input"))
      (node (ref "R3") (pin "1") (pinfunction "1_1") (pintype "passive"))
    )
    (net (code "55") (name "Net-(IC6-FB)") (class "Default")
      (node (ref "C26") (pin "1") (pinfunction "1_1") (pintype "passive"))
      (node (ref "IC6") (pin "4") (pinfunction "FB_4") (pintype "input"))
      (node (ref "R10") (pin "1") (pinfunction "1_1") (pintype "passive"))
      (node (ref "R8") (pin "1") (pinfunction "1_1") (pintype "passive"))
    )
    (net (code "56") (name "Net-(IC6-OUT)") (class "Default")
      (node (ref "D2") (pin "C") (pinfunction "C_C") (pintype "passive"))
      (node (ref "IC6") (pin "8") (pinfunction "OUT_8") (pintype "output"))
      (node (ref "L11") (pin "1") (pinfunction "1_1") (pintype "passive"))
    )
    (net (code "57") (name "Net-(IC7-BYP)") (class "Default")
      (node (ref "C29") (pin "1") (pinfunction "1_1") (pintype "passive"))
      (node (ref "IC7") (pin "4") (pinfunction "BYP_4") (pintype "passive"))
      (node (ref "R19") (pin "2") (pinfunction "2_2") (pintype "passive"))
      (node (ref "R20") (pin "2") (pinfunction "2_2") (pintype "passive"))
    )
    (net (code "58") (name "Net-(IC7-OUT)") (class "Default")
      (node (ref "C30") (pin "1") (pinfunction "1_1") (pintype "passive"))
      (node (ref "DISPLAY") (pin "1") (pinfunction "1_1") (pintype "passive"))
      (node (ref "IC7") (pin "5") (pinfunction "OUT_5") (pintype "output"))
      (node (ref "R20") (pin "1") (pinfunction "1_1") (pintype "passive"))
    )
    (net (code "59") (name "Net-(LED1-PadC)") (class "Default")
      (node (ref "LED1") (pin "C") (pinfunction "C_C") (pintype "passive"))
      (node (ref "R25") (pin "2") (pinfunction "2_2") (pintype "passive"))
    )
    (net (code "60") (name "Net-(Q2-B)") (class "Default")
      (node (ref "Q2") (pin "1") (pinfunction "B_1") (pintype "passive"))
      (node (ref "R6") (pin "1") (pinfunction "1_1") (pintype "passive"))
    )
    (net (code "61") (name "Net-(Q3-B)") (class "Default")
      (node (ref "Q3") (pin "1") (pinfunction "B_1") (pintype "passive"))
      (node (ref "R7") (pin "1") (pinfunction "1_1") (pintype "passive"))
    )
    (net (code "62") (name "Net-(R10-Pad2)") (class "Default")
      (node (ref "R10") (pin "2") (pinfunction "2_2") (pintype "passive"))
      (node (ref "R11") (pin "1") (pinfunction "1_1") (pintype "passive"))
    )
    (net (code "63") (name "Net-(X2A-KL)") (class "Default")
      (node (ref "K1") (pin "O") (pinfunction "O_O") (pintype "passive"))
      (node (ref "X2") (pin "1") (pinfunction "KL_1") (pintype "passive"))
    )
    (net (code "64") (name "Net-(X2B-KL)") (class "Default")
      (node (ref "K1") (pin "S") (pinfunction "S_S") (pintype "passive"))
      (node (ref "X2") (pin "2") (pinfunction "KL_2") (pintype "passive"))
    )
    (net (code "65") (name "Net-(X2C-KL)") (class "Default")
      (node (ref "K1") (pin "P") (pinfunction "P_P") (pintype "passive"))
      (node (ref "X2") (pin "3") (pinfunction "KL_3") (pintype "passive"))
    )
    (net (code "66") (name "Net-(X3A-KL)") (class "Default")
      (node (ref "K2") (pin "S") (pinfunction "S_S") (pintype "passive"))
      (node (ref "X3") (pin "1") (pinfunction "KL_1") (pintype "passive"))
    )
    (net (code "67") (name "Net-(X3B-KL)") (class "Default")
      (node (ref "K2") (pin "P") (pinfunction "P_P") (pintype "passive"))
      (node (ref "X3") (pin "2") (pinfunction "KL_2") (pintype "passive"))
    )
    (net (code "68") (name "Net-(X3C-KL)") (class "Default")
      (node (ref "K2") (pin "O") (pinfunction "O_O") (pintype "passive"))
      (node (ref "X3") (pin "3") (pinfunction "KL_3") (pintype "passive"))
    )
    (net (code "69") (name "Net-(X4-B-2)") (class "Default")
      (node (ref "J1") (pin "3") (pinfunction "3_3") (pintype "passive"))
      (node (ref "J2") (pin "3") (pinfunction "3_3") (pintype "passive"))
      (node (ref "R1") (pin "2") (pinfunction "2_2") (pintype "passive"))
      (node (ref "R2") (pin "1") (pinfunction "1_1") (pintype "passive"))
      (node (ref "X4") (pin "B2") (pinfunction "B-2_B2") (pintype "passive"))
    )
    (net (code "70") (name "Net-(X4-B-3)") (class "Default")
      (node (ref "J1") (pin "4") (pinfunction "4_4") (pintype "passive"))
      (node (ref "J2") (pin "4") (pinfunction "4_4") (pintype "passive"))
      (node (ref "R17") (pin "1") (pinfunction "1_1") (pintype "passive"))
      (node (ref "X4") (pin "B3") (pinfunction "B-3_B3") (pintype "passive"))
    )
    (net (code "71") (name "Net-(X4-B-4)") (class "Default")
      (node (ref "J1") (pin "5") (pinfunction "5_5") (pintype "passive"))
      (node (ref "J2") (pin "5") (pinfunction "5_5") (pintype "passive"))
      (node (ref "R16") (pin "1") (pinfunction "1_1") (pintype "passive"))
      (node (ref "X4") (pin "B4") (pinfunction "B-4_B4") (pintype "passive"))
    )
    (net (code "72") (name "Net-(X4-B-5)") (class "Default")
      (node (ref "J1") (pin "6") (pinfunction "6_6") (pintype "passive"))
      (node (ref "J2") (pin "6") (pinfunction "6_6") (pintype "passive"))
      (node (ref "R1") (pin "1") (pinfunction "1_1") (pintype "passive"))
      (node (ref "X4") (pin "B5") (pinfunction "B-5_B5") (pintype "passive"))
    )
    (net (code "73") (name "Net-(X6--1)") (class "Default")
      (node (ref "C16") (pin "1") (pinfunction "1_1") (pintype "passive"))
      (node (ref "L1") (pin "1") (pinfunction "1_1") (pintype "passive"))
      (node (ref "X6") (pin "A1") (pinfunction "-1_A1") (pintype "passive"))
    )
    (net (code "74") (name "Net-(X6--2)") (class "Default")
      (node (ref "C15") (pin "1") (pinfunction "1_1") (pintype "passive"))
      (node (ref "L2") (pin "1") (pinfunction "1_1") (pintype "passive"))
      (node (ref "X6") (pin "A2") (pinfunction "-2_A2") (pintype "passive"))
    )
    (net (code "75") (name "Net-(X6--3)") (class "Default")
      (node (ref "C14") (pin "1") (pinfunction "1_1") (pintype "passive"))
      (node (ref "L3") (pin "1") (pinfunction "1_1") (pintype "passive"))
      (node (ref "X6") (pin "A3") (pinfunction "-3_A3") (pintype "passive"))
    )
    (net (code "76") (name "Net-(X6--4)") (class "Default")
      (node (ref "C13") (pin "1") (pinfunction "1_1") (pintype "passive"))
      (node (ref "L4") (pin "1") (pinfunction "1_1") (pintype "passive"))
      (node (ref "X6") (pin "A4") (pinfunction "-4_A4") (pintype "passive"))
    )
    (net (code "77") (name "Net-(X6--5)") (class "Default")
      (node (ref "C12") (pin "1") (pinfunction "1_1") (pintype "passive"))
      (node (ref "L5") (pin "1") (pinfunction "1_1") (pintype "passive"))
      (node (ref "X6") (pin "A5") (pinfunction "-5_A5") (pintype "passive"))
    )
    (net (code "78") (name "Net-(X6--6)") (class "Default")
      (node (ref "C11") (pin "1") (pinfunction "1_1") (pintype "passive"))
      (node (ref "L6") (pin "1") (pinfunction "1_1") (pintype "passive"))
      (node (ref "X6") (pin "A6") (pinfunction "-6_A6") (pintype "passive"))
    )
    (net (code "79") (name "Net-(X6--7)") (class "Default")
      (node (ref "C10") (pin "1") (pinfunction "1_1") (pintype "passive"))
      (node (ref "L7") (pin "1") (pinfunction "1_1") (pintype "passive"))
      (node (ref "X6") (pin "A7") (pinfunction "-7_A7") (pintype "passive"))
    )
    (net (code "80") (name "Net-(X6--8)") (class "Default")
      (node (ref "C9") (pin "1") (pinfunction "1_1") (pintype "passive"))
      (node (ref "L8") (pin "1") (pinfunction "1_1") (pintype "passive"))
      (node (ref "X6") (pin "A8") (pinfunction "-8_A8") (pintype "passive"))
    )
    (net (code "81") (name "Net-(X6--9)") (class "Default")
      (node (ref "C8") (pin "1") (pinfunction "1_1") (pintype "passive"))
      (node (ref "L9") (pin "1") (pinfunction "1_1") (pintype "passive"))
      (node (ref "X6") (pin "A9") (pinfunction "-9_A9") (pintype "passive"))
    )
    (net (code "82") (name "Net-(X6--10)") (class "Default")
      (node (ref "C7") (pin "1") (pinfunction "1_1") (pintype "passive"))
      (node (ref "L10") (pin "1") (pinfunction "1_1") (pintype "passive"))
      (node (ref "X6") (pin "A10") (pinfunction "-10_A10") (pintype "passive"))
    )
    (net (code "83") (name "Net-(X7--1)") (class "Default")
      (node (ref "R14") (pin "2") (pinfunction "2_2") (pintype "passive"))
      (node (ref "X7") (pin "A1") (pinfunction "-1_A1") (pintype "passive"))
    )
    (net (code "84") (name "Net-(X7--3)") (class "Default")
      (node (ref "R15") (pin "2") (pinfunction "2_2") (pintype "passive"))
      (node (ref "X7") (pin "A3") (pinfunction "-3_A3") (pintype "passive"))
    )
    (net (code "85") (name "Net-(X9A-KL)") (class "Default")
      (node (ref "D1") (pin "A") (pinfunction "A_A") (pintype "passive"))
      (node (ref "X9") (pin "1") (pinfunction "KL_1") (pintype "passive"))
    )
    (net (code "86") (name "Net-(X9C-KL)") (class "Default")
      (node (ref "F2") (pin "2A") (pinfunction "2A_2A") (pintype "passive"))
      (node (ref "X9") (pin "3") (pinfunction "KL_3") (pintype "passive"))
    )
    (net (code "87") (name "V+") (class "Default")
      (node (ref "D1") (pin "C") (pinfunction "C_C") (pintype "passive"))
      (node (ref "D6") (pin "1") (pinfunction "K1_1") (pintype "passive"))
      (node (ref "D6") (pin "2") (pinfunction "K2_2") (pintype "passive"))
      (node (ref "F1") (pin "1A") (pinfunction "1A_1A") (pintype "passive"))
      (node (ref "F2") (pin "1A") (pinfunction "1A_1A") (pintype "passive"))
      (node (ref "J1") (pin "1") (pinfunction "1_1") (pintype "passive"))
      (node (ref "J1") (pin "2") (pinfunction "2_2") (pintype "passive"))
      (node (ref "J2") (pin "1") (pinfunction "1_1") (pintype "passive"))
      (node (ref "J2") (pin "2") (pinfunction "2_2") (pintype "passive"))
      (node (ref "X4") (pin "B1") (pinfunction "B-1_B1") (pintype "passive"))
    )
    (net (code "88") (name "unconnected-(DISPLAY-Pad7)") (class "Default")
      (node (ref "DISPLAY") (pin "7") (pinfunction "7_7") (pintype "passive"))
    )
    (net (code "89") (name "unconnected-(DISPLAY-Pad9)") (class "Default")
      (node (ref "DISPLAY") (pin "9") (pinfunction "9_9") (pintype "passive"))
    )
    (net (code "90") (name "unconnected-(DISPLAY-Pad10)") (class "Default")
      (node (ref "DISPLAY") (pin "10") (pinfunction "10_10") (pintype "passive"))
    )
    (net (code "91") (name "unconnected-(F1-Pad1B)") (class "Default")
      (node (ref "F1") (pin "1B") (pinfunction "1B_1B") (pintype "passive"))
    )
    (net (code "92") (name "unconnected-(F1-Pad2B)") (class "Default")
      (node (ref "F1") (pin "2B") (pinfunction "2B_2B") (pintype "passive"))
    )
    (net (code "93") (name "unconnected-(F2-Pad1B)") (class "Default")
      (node (ref "F2") (pin "1B") (pinfunction "1B_1B") (pintype "passive"))
    )
    (net (code "94") (name "unconnected-(F2-Pad2B)") (class "Default")
      (node (ref "F2") (pin "2B") (pinfunction "2B_2B") (pintype "passive"))
    )
    (net (code "95") (name "unconnected-(IC4-PFO-Pad5)") (class "Default")
      (node (ref "IC4") (pin "5") (pinfunction "PFO_5") (pintype "output"))
    )
    (net (code "96") (name "unconnected-(IC4-WDO-Pad8)") (class "Default")
      (node (ref "IC4") (pin "8") (pinfunction "WDO_8") (pintype "output"))
    )
    (net (code "97") (name "unconnected-(JTAG-Pad7)") (class "Default")
      (node (ref "JTAG") (pin "7") (pinfunction "7_7") (pintype "passive"))
    )
    (net (code "98") (name "unconnected-(JTAG-Pad8)") (class "Default")
      (node (ref "JTAG") (pin "8") (pinfunction "8_8") (pintype "passive"))
    )
    (net (code "99") (name "unconnected-(X1-B-1-PadB1)") (class "Default")
      (node (ref "X1") (pin "B1") (pinfunction "B-1_B1") (pintype "passive"))
    )
    (net (code "100") (name "unconnected-(X1-B-2-PadB2)") (class "Default")
      (node (ref "X1") (pin "B2") (pinfunction "B-2_B2") (pintype "passive"))
    )
    (net (code "101") (name "unconnected-(X4--1-PadA1)") (class "Default")
      (node (ref "X4") (pin "A1") (pinfunction "-1_A1") (pintype "passive"))
    )
    (net (code "102") (name "unconnected-(X4--2-PadA2)") (class "Default")
      (node (ref "X4") (pin "A2") (pinfunction "-2_A2") (pintype "passive"))
    )
    (net (code "103") (name "unconnected-(X4--3-PadA3)") (class "Default")
      (node (ref "X4") (pin "A3") (pinfunction "-3_A3") (pintype "passive"))
    )
    (net (code "104") (name "unconnected-(X4--4-PadA4)") (class "Default")
      (node (ref "X4") (pin "A4") (pinfunction "-4_A4") (pintype "passive"))
    )
    (net (code "105") (name "unconnected-(X4--5-PadA5)") (class "Default")
      (node (ref "X4") (pin "A5") (pinfunction "-5_A5") (pintype "passive"))
    )
    (net (code "106") (name "unconnected-(X4--6-PadA6)") (class "Default")
      (node (ref "X4") (pin "A6") (pinfunction "-6_A6") (pintype "passive"))
    )
    (net (code "107") (name "unconnected-(X5-B-1-PadB1)") (class "Default")
      (node (ref "X5") (pin "B1") (pinfunction "B-1_B1") (pintype "passive"))
    )
    (net (code "108") (name "unconnected-(X5-B-2-PadB2)") (class "Default")
      (node (ref "X5") (pin "B2") (pinfunction "B-2_B2") (pintype "passive"))
    )
    (net (code "109") (name "unconnected-(X5-B-3-PadB3)") (class "Default")
      (node (ref "X5") (pin "B3") (pinfunction "B-3_B3") (pintype "passive"))
    )
    (net (code "110") (name "unconnected-(X5-B-4-PadB4)") (class "Default")
      (node (ref "X5") (pin "B4") (pinfunction "B-4_B4") (pintype "passive"))
    )
    (net (code "111") (name "unconnected-(X5-B-5-PadB5)") (class "Default")
      (node (ref "X5") (pin "B5") (pinfunction "B-5_B5") (pintype "passive"))
    )
    (net (code "112") (name "unconnected-(X5-B-6-PadB6)") (class "Default")
      (node (ref "X5") (pin "B6") (pinfunction "B-6_B6") (pintype "passive"))
    )
    (net (code "113") (name "unconnected-(X6-B-1-PadB1)") (class "Default")
      (node (ref "X6") (pin "B1") (pinfunction "B-1_B1") (pintype "passive"))
    )
    (net (code "114") (name "unconnected-(X6-B-2-PadB2)") (class "Default")
      (node (ref "X6") (pin "B2") (pinfunction "B-2_B2") (pintype "passive"))
    )
    (net (code "115") (name "unconnected-(X6-B-3-PadB3)") (class "Default")
      (node (ref "X6") (pin "B3") (pinfunction "B-3_B3") (pintype "passive"))
    )
    (net (code "116") (name "unconnected-(X6-B-4-PadB4)") (class "Default")
      (node (ref "X6") (pin "B4") (pinfunction "B-4_B4") (pintype "passive"))
    )
    (net (code "117") (name "unconnected-(X6-B-5-PadB5)") (class "Default")
      (node (ref "X6") (pin "B5") (pinfunction "B-5_B5") (pintype "passive"))
    )
    (net (code "118") (name "unconnected-(X6-B-6-PadB6)") (class "Default")
      (node (ref "X6") (pin "B6") (pinfunction "B-6_B6") (pintype "passive"))
    )
    (net (code "119") (name "unconnected-(X6-B-7-PadB7)") (class "Default")
      (node (ref "X6") (pin "B7") (pinfunction "B-7_B7") (pintype "passive"))
    )
    (net (code "120") (name "unconnected-(X6-B-8-PadB8)") (class "Default")
      (node (ref "X6") (pin "B8") (pinfunction "B-8_B8") (pintype "passive"))
    )
    (net (code "121") (name "unconnected-(X6-B-9-PadB9)") (class "Default")
      (node (ref "X6") (pin "B9") (pinfunction "B-9_B9") (pintype "passive"))
    )
    (net (code "122") (name "unconnected-(X6-B-10-PadB10)") (class "Default")
      (node (ref "X6") (pin "B10") (pinfunction "B-10_B10") (pintype "passive"))
    )
    (net (code "123") (name "unconnected-(X6-B-11-PadB11)") (class "Default")
      (node (ref "X6") (pin "B11") (pinfunction "B-11_B11") (pintype "passive"))
    )
    (net (code "124") (name "unconnected-(X6-B-12-PadB12)") (class "Default")
      (node (ref "X6") (pin "B12") (pinfunction "B-12_B12") (pintype "passive"))
    )
    (net (code "125") (name "unconnected-(X7-B-1-PadB1)") (class "Default")
      (node (ref "X7") (pin "B1") (pinfunction "B-1_B1") (pintype "passive"))
    )
    (net (code "126") (name "unconnected-(X7-B-2-PadB2)") (class "Default")
      (node (ref "X7") (pin "B2") (pinfunction "B-2_B2") (pintype "passive"))
    )
    (net (code "127") (name "unconnected-(X7-B-3-PadB3)") (class "Default")
      (node (ref "X7") (pin "B3") (pinfunction "B-3_B3") (pintype "passive"))
    )
    (net (code "128") (name "unconnected-(X7-B-4-PadB4)") (class "Default")
      (node (ref "X7") (pin "B4") (pinfunction "B-4_B4") (pintype "passive"))
    )
    (net (code "129") (name "unconnected-(X8--1-PadA1)") (class "Default")
      (node (ref "X8") (pin "A1") (pinfunction "-1_A1") (pintype "passive"))
    )
    (net (code "130") (name "unconnected-(X8--2-PadA2)") (class "Default")
      (node (ref "X8") (pin "A2") (pinfunction "-2_A2") (pintype "passive"))
    )
    (net (code "131") (name "unconnected-(X8--3-PadA3)") (class "Default")
      (node (ref "X8") (pin "A3") (pinfunction "-3_A3") (pintype "passive"))
    )
    (net (code "132") (name "unconnected-(X8--4-PadA4)") (class "Default")
      (node (ref "X8") (pin "A4") (pinfunction "-4_A4") (pintype "passive"))
    )
  )
)
